# VCA821_AGC.net
KiCad netlist of a schematic drawn in Altium Designer
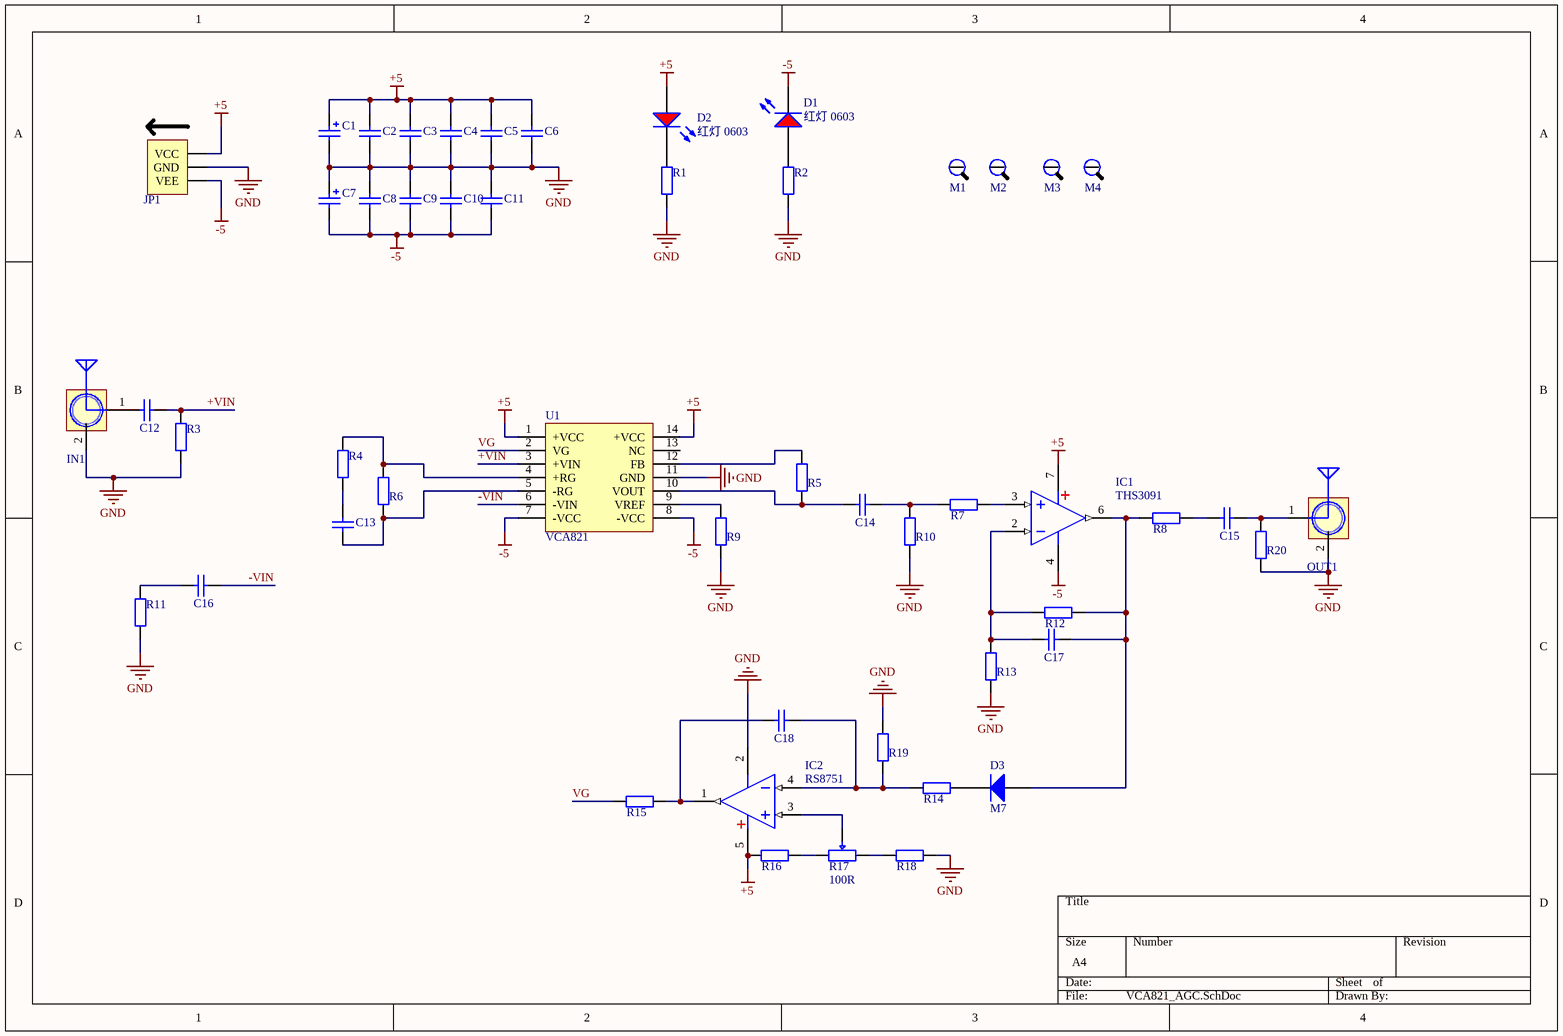
[diagram p0: VCA821_AGC.SchDoc]

(export (version "E")
  (design (tool "Eeschema 10.0.6"))
  (components
    (comp (ref "C1")
      (value "10uF (106) ±10% 16V")
      (footprint "CASE-A_3216")
      (description "钽电容")
      (libsource (lib "JLC") (part "3216 10uF (106) 10% 16V"))
    )
    (comp (ref "C2")
      (value "100nF (104) 10% 50V")
      (footprint "0603_C")
      (description "贴片电容")
      (libsource (lib "JLC") (part "0603 100nF (104) 10% 50V"))
    )
    (comp (ref "C3")
      (value "100nF (104) 10% 50V")
      (footprint "0603_C")
      (description "贴片电容")
      (libsource (lib "JLC") (part "0603 100nF (104) 10% 50V"))
    )
    (comp (ref "C4")
      (value "100nF (104) 10% 50V")
      (footprint "0603_C")
      (description "贴片电容")
      (libsource (lib "JLC") (part "0603 100nF (104) 10% 50V"))
    )
    (comp (ref "C5")
      (value "100nF (104) 10% 50V")
      (footprint "0603_C")
      (description "贴片电容")
      (libsource (lib "JLC") (part "0603 100nF (104) 10% 50V"))
    )
    (comp (ref "C6")
      (value "100nF (104) 10% 50V")
      (footprint "0603_C")
      (description "贴片电容")
      (libsource (lib "JLC") (part "0603 100nF (104) 10% 50V"))
    )
    (comp (ref "C7")
      (value "10uF (106) ±10% 16V")
      (footprint "CASE-A_3216")
      (description "钽电容")
      (libsource (lib "JLC") (part "3216 10uF (106) 10% 16V"))
    )
    (comp (ref "C8")
      (value "100nF (104) 10% 50V")
      (footprint "0603_C")
      (description "贴片电容")
      (libsource (lib "JLC") (part "0603 100nF (104) 10% 50V"))
    )
    (comp (ref "C9")
      (value "100nF (104) 10% 50V")
      (footprint "0603_C")
      (description "贴片电容")
      (libsource (lib "JLC") (part "0603 100nF (104) 10% 50V"))
    )
    (comp (ref "C10")
      (value "100nF (104) 10% 50V")
      (footprint "0603_C")
      (description "贴片电容")
      (libsource (lib "JLC") (part "0603 100nF (104) 10% 50V"))
    )
    (comp (ref "C11")
      (value "100nF (104) 10% 50V")
      (footprint "0603_C")
      (description "贴片电容")
      (libsource (lib "JLC") (part "0603 100nF (104) 10% 50V"))
    )
    (comp (ref "C12")
      (value "100nF (104) 10% 50V")
      (footprint "0603_C")
      (description "贴片电容")
      (libsource (lib "JLC") (part "0603 100nF (104) 10% 50V"))
    )
    (comp (ref "C13")
      (value "100nF (104) 10% 50V")
      (footprint "0603_C")
      (description "贴片电容")
      (libsource (lib "JLC") (part "0603 100nF (104) 10% 50V"))
    )
    (comp (ref "C14")
      (value "100nF (104) 10% 50V")
      (footprint "0603_C")
      (description "贴片电容")
      (libsource (lib "JLC") (part "0603 100nF (104) 10% 50V"))
    )
    (comp (ref "C15")
      (value "100nF (104) 10% 50V")
      (footprint "0603_C")
      (description "贴片电容")
      (libsource (lib "JLC") (part "0603 100nF (104) 10% 50V"))
    )
    (comp (ref "C16")
      (value "100nF (104) 10% 50V")
      (footprint "0603_C")
      (description "贴片电容")
      (libsource (lib "JLC") (part "0603 100nF (104) 10% 50V"))
    )
    (comp (ref "C17")
      (value "100nF (104) 10% 50V")
      (footprint "0603_C")
      (description "贴片电容")
      (libsource (lib "JLC") (part "0603 100nF (104) 10% 50V"))
    )
    (comp (ref "C18")
      (value "100nF (104) 10% 50V")
      (footprint "0603_C")
      (description "贴片电容")
      (libsource (lib "JLC") (part "0603 100nF (104) 10% 50V"))
    )
    (comp (ref "D1")
      (value "红灯 0603")
      (footprint "0603_LED_S1")
      (description "发光二极管")
      (libsource (lib "JLC") (part "0603 红灯"))
    )
    (comp (ref "D2")
      (value "红灯 0603")
      (footprint "0603_LED_S1")
      (description "发光二极管")
      (libsource (lib "JLC") (part "0603 红灯"))
    )
    (comp (ref "D3")
      (value "M7")
      (footprint "SMA(DO-214AC)_S1")
      (description "二极管")
      (libsource (lib "JLC") (part "SMA(DO-214AC) M7"))
    )
    (comp (ref "IC1")
      (value "THS3091")
      (footprint "SOP8_N")
      (description "SOP8_轨至轨运放")
      (fields (field (name "版权归属") "源创客"))
      (libsource (lib "1.5   - 运放-功放") (part "SGM8521-8Pin"))
    )
    (comp (ref "IC2")
      (value "RS8751")
      (footprint "SOT23-5N")
      (description "SOT23-5_轨至轨运放")
      (fields (field (name "版权归属") "源创客"))
      (libsource (lib "1.5   - 运放-功放") (part "SGM8521-5Pin"))
    )
    (comp (ref "IN1")
      (value "SMA WIFI 天线接口")
      (footprint "SMA")
      (description "SMA-2.4G射频天线接口")
      (fields (field (name "版权归属") "源创客"))
      (libsource (lib "") (part "PORT_SMA_1"))
    )
    (comp (ref "JP1")
      (value "HDR-1X3")
      (footprint "Power_IN_3.81-3P")
      (description "3P接插件,模块双电源供电口")
      (fields (field (name "版权归属") "源创客"))
      (libsource (lib "Cooperation") (part "PORT_Power_IN3"))
    )
    (comp (ref "M1")
      (value "M3")
      (footprint "M3x10_L")
      (description "螺丝")
      (libsource (lib "Cooperation") (part "ELSE_M3_screw"))
    )
    (comp (ref "M2")
      (value "M3")
      (footprint "M3x10_L")
      (description "螺丝")
      (libsource (lib "Cooperation") (part "ELSE_M3_screw"))
    )
    (comp (ref "M3")
      (value "M3")
      (footprint "M3x10_L")
      (description "螺丝")
      (libsource (lib "Cooperation") (part "ELSE_M3_screw"))
    )
    (comp (ref "M4")
      (value "M3")
      (footprint "M3x10_L")
      (description "螺丝")
      (libsource (lib "Cooperation") (part "ELSE_M3_screw"))
    )
    (comp (ref "OUT1")
      (value "SMA WIFI 天线接口")
      (footprint "SMA")
      (description "SMA-2.4G射频天线接口")
      (fields (field (name "版权归属") "源创客"))
      (libsource (lib "Cooperation") (part "PORT_SMA"))
    )
    (comp (ref "R1")
      (value "10KΩ (1002) ±1%")
      (footprint "0603_R")
      (description "贴片电阻")
      (libsource (lib "JLC") (part "0603 10KΩ (1002) 1%"))
    )
    (comp (ref "R2")
      (value "10KΩ (1002) ±1%")
      (footprint "0603_R")
      (description "贴片电阻")
      (libsource (lib "JLC") (part "0603 10KΩ (1002) 1%"))
    )
    (comp (ref "R3")
      (value "10KΩ (1002) ±1%")
      (footprint "0603_R")
      (description "贴片电阻")
      (libsource (lib "JLC") (part "0603 10KΩ (1002) 1%"))
    )
    (comp (ref "R4")
      (value "10KΩ (1002) ±1%")
      (footprint "0603_R")
      (description "贴片电阻")
      (libsource (lib "JLC") (part "0603 10KΩ (1002) 1%"))
    )
    (comp (ref "R5")
      (value "10KΩ (1002) ±1%")
      (footprint "0603_R")
      (description "贴片电阻")
      (libsource (lib "") (part "0603 10KΩ (1002) 1%_1"))
    )
    (comp (ref "R6")
      (value "10KΩ (1002) ±1%")
      (footprint "0603_R")
      (description "贴片电阻")
      (libsource (lib "") (part "0603 10KΩ (1002) 1%_1"))
    )
    (comp (ref "R7")
      (value "10KΩ (1002) ±1%")
      (footprint "0603_R")
      (description "贴片电阻")
      (libsource (lib "") (part "0603 10KΩ (1002) 1%_2"))
    )
    (comp (ref "R8")
      (value "10KΩ (1002) ±1%")
      (footprint "0603_R")
      (description "贴片电阻")
      (libsource (lib "") (part "0603 10KΩ (1002) 1%_2"))
    )
    (comp (ref "R9")
      (value "10KΩ (1002) ±1%")
      (footprint "0603_R")
      (description "贴片电阻")
      (libsource (lib "") (part "0603 10KΩ (1002) 1%_1"))
    )
    (comp (ref "R10")
      (value "10KΩ (1002) ±1%")
      (footprint "0603_R")
      (description "贴片电阻")
      (libsource (lib "") (part "0603 10KΩ (1002) 1%_1"))
    )
    (comp (ref "R11")
      (value "10KΩ (1002) ±1%")
      (footprint "0603_R")
      (description "贴片电阻")
      (libsource (lib "JLC") (part "0603 10KΩ (1002) 1%"))
    )
    (comp (ref "R12")
      (value "10KΩ (1002) ±1%")
      (footprint "0603_R")
      (description "贴片电阻")
      (libsource (lib "") (part "0603 10KΩ (1002) 1%_2"))
    )
    (comp (ref "R13")
      (value "10KΩ (1002) ±1%")
      (footprint "0603_R")
      (description "贴片电阻")
      (libsource (lib "") (part "0603 10KΩ (1002) 1%_1"))
    )
    (comp (ref "R14")
      (value "10KΩ (1002) ±1%")
      (footprint "0603_R")
      (description "贴片电阻")
      (libsource (lib "") (part "0603 10KΩ (1002) 1%_2"))
    )
    (comp (ref "R15")
      (value "10KΩ (1002) ±1%")
      (footprint "0603_R")
      (description "贴片电阻")
      (libsource (lib "") (part "0603 10KΩ (1002) 1%_2"))
    )
    (comp (ref "R16")
      (value "10KΩ (1002) ±1%")
      (footprint "0603_R")
      (description "贴片电阻")
      (libsource (lib "") (part "0603 10KΩ (1002) 1%_2"))
    )
    (comp (ref "R17")
      (value "100R")
      (footprint "adjustable resistor")
      (description "adjustable resistor可调电阻")
      (fields (field (name "Comment") "Ω"))
      (libsource (lib "Cooperation") (part "RES_Adjustable_Resistor"))
    )
    (comp (ref "R18")
      (value "10KΩ (1002) ±1%")
      (footprint "0603_R")
      (description "贴片电阻")
      (libsource (lib "") (part "0603 10KΩ (1002) 1%_2"))
    )
    (comp (ref "R19")
      (value "10KΩ (1002) ±1%")
      (footprint "0603_R")
      (description "贴片电阻")
      (libsource (lib "JLC") (part "0603 10KΩ (1002) 1%"))
    )
    (comp (ref "R20")
      (value "10KΩ (1002) ±1%")
      (footprint "0603_R")
      (description "贴片电阻")
      (libsource (lib "JLC") (part "0603 10KΩ (1002) 1%"))
    )
    (comp (ref "U1") (value "VCA821") (footprint "SO-14N") (libsource (lib "Cooperation") (part "VCA821")))
  )
  (nets
    (net (code "1") (name "+5") (class "Default")
      (node (ref "C1") (pin "1") (pinfunction "1_1") (pintype "passive"))
      (node (ref "C2") (pin "2") (pinfunction "2_2") (pintype "passive"))
      (node (ref "C3") (pin "2") (pinfunction "2_2") (pintype "passive"))
      (node (ref "C4") (pin "2") (pinfunction "2_2") (pintype "passive"))
      (node (ref "C5") (pin "2") (pinfunction "2_2") (pintype "passive"))
      (node (ref "C6") (pin "2") (pinfunction "2_2") (pintype "passive"))
      (node (ref "D2") (pin "A") (pinfunction "A_A") (pintype "passive"))
      (node (ref "IC1") (pin "7") (pinfunction "V+_7") (pintype "power_in"))
      (node (ref "IC2") (pin "5") (pinfunction "V+_5") (pintype "power_in"))
      (node (ref "JP1") (pin "1") (pinfunction "VCC_1") (pintype "passive"))
      (node (ref "R16") (pin "1") (pinfunction "1_1") (pintype "passive"))
      (node (ref "U1") (pin "1") (pinfunction "+VCC_1") (pintype "passive"))
      (node (ref "U1") (pin "14") (pinfunction "+VCC_14") (pintype "passive"))
    )
    (net (code "2") (name "-5") (class "Default")
      (node (ref "C10") (pin "1") (pinfunction "1_1") (pintype "passive"))
      (node (ref "C11") (pin "1") (pinfunction "1_1") (pintype "passive"))
      (node (ref "C7") (pin "2") (pinfunction "2_2") (pintype "passive"))
      (node (ref "C8") (pin "1") (pinfunction "1_1") (pintype "passive"))
      (node (ref "C9") (pin "1") (pinfunction "1_1") (pintype "passive"))
      (node (ref "D1") (pin "K") (pinfunction "K_K") (pintype "passive"))
      (node (ref "IC1") (pin "4") (pinfunction "V-_4") (pintype "power_in"))
      (node (ref "JP1") (pin "3") (pinfunction "VEE_3") (pintype "passive"))
      (node (ref "U1") (pin "7") (pinfunction "-VCC_7") (pintype "passive"))
      (node (ref "U1") (pin "8") (pinfunction "-VCC_8") (pintype "passive"))
    )
    (net (code "3") (name "/+VIN") (class "Default")
      (node (ref "C12") (pin "1") (pinfunction "1_1") (pintype "passive"))
      (node (ref "R3") (pin "2") (pinfunction "2_2") (pintype "passive"))
      (node (ref "U1") (pin "3") (pinfunction "+VIN_3") (pintype "passive"))
    )
    (net (code "4") (name "/-VIN") (class "Default")
      (node (ref "C16") (pin "1") (pinfunction "1_1") (pintype "passive"))
      (node (ref "U1") (pin "6") (pinfunction "-VIN_6") (pintype "passive"))
    )
    (net (code "5") (name "/VG") (class "Default")
      (node (ref "R15") (pin "1") (pinfunction "1_1") (pintype "passive"))
      (node (ref "U1") (pin "2") (pinfunction "VG_2") (pintype "passive"))
    )
    (net (code "6") (name "GND") (class "Default")
      (node (ref "C1") (pin "2") (pinfunction "2_2") (pintype "passive"))
      (node (ref "C10") (pin "2") (pinfunction "2_2") (pintype "passive"))
      (node (ref "C11") (pin "2") (pinfunction "2_2") (pintype "passive"))
      (node (ref "C2") (pin "1") (pinfunction "1_1") (pintype "passive"))
      (node (ref "C3") (pin "1") (pinfunction "1_1") (pintype "passive"))
      (node (ref "C4") (pin "1") (pinfunction "1_1") (pintype "passive"))
      (node (ref "C5") (pin "1") (pinfunction "1_1") (pintype "passive"))
      (node (ref "C6") (pin "1") (pinfunction "1_1") (pintype "passive"))
      (node (ref "C7") (pin "1") (pinfunction "1_1") (pintype "passive"))
      (node (ref "C8") (pin "2") (pinfunction "2_2") (pintype "passive"))
      (node (ref "C9") (pin "2") (pinfunction "2_2") (pintype "passive"))
      (node (ref "IC2") (pin "2") (pinfunction "V-_2") (pintype "power_in"))
      (node (ref "IN1") (pin "2") (pinfunction "2_2") (pintype "passive"))
      (node (ref "JP1") (pin "2") (pinfunction "GND_2") (pintype "passive"))
      (node (ref "OUT1") (pin "2") (pinfunction "2_2") (pintype "passive"))
      (node (ref "R1") (pin "1") (pinfunction "1_1") (pintype "passive"))
      (node (ref "R10") (pin "2") (pinfunction "2_2") (pintype "passive"))
      (node (ref "R11") (pin "1") (pinfunction "1_1") (pintype "passive"))
      (node (ref "R13") (pin "2") (pinfunction "2_2") (pintype "passive"))
      (node (ref "R18") (pin "2") (pinfunction "2_2") (pintype "passive"))
      (node (ref "R19") (pin "2") (pinfunction "2_2") (pintype "passive"))
      (node (ref "R2") (pin "1") (pinfunction "1_1") (pintype "passive"))
      (node (ref "R20") (pin "1") (pinfunction "1_1") (pintype "passive"))
      (node (ref "R3") (pin "1") (pinfunction "1_1") (pintype "passive"))
      (node (ref "R9") (pin "2") (pinfunction "2_2") (pintype "passive"))
      (node (ref "U1") (pin "11") (pinfunction "GND_11") (pintype "passive"))
    )
    (net (code "7") (name "Net-(C13-Pad2)") (class "Default")
      (node (ref "C13") (pin "2") (pinfunction "2_2") (pintype "passive"))
      (node (ref "R4") (pin "1") (pinfunction "1_1") (pintype "passive"))
    )
    (net (code "8") (name "Net-(C14-Pad1)") (class "Default")
      (node (ref "C14") (pin "1") (pinfunction "1_1") (pintype "passive"))
      (node (ref "R10") (pin "1") (pinfunction "1_1") (pintype "passive"))
      (node (ref "R7") (pin "1") (pinfunction "1_1") (pintype "passive"))
    )
    (net (code "9") (name "Net-(C15-Pad2)") (class "Default")
      (node (ref "C15") (pin "2") (pinfunction "2_2") (pintype "passive"))
      (node (ref "R8") (pin "2") (pinfunction "2_2") (pintype "passive"))
    )
    (net (code "10") (name "Net-(C16-Pad2)") (class "Default")
      (node (ref "C16") (pin "2") (pinfunction "2_2") (pintype "passive"))
      (node (ref "R11") (pin "2") (pinfunction "2_2") (pintype "passive"))
    )
    (net (code "11") (name "Net-(D1-PadA)") (class "Default")
      (node (ref "D1") (pin "A") (pinfunction "A_A") (pintype "passive"))
      (node (ref "R2") (pin "2") (pinfunction "2_2") (pintype "passive"))
    )
    (net (code "12") (name "Net-(D2-PadK)") (class "Default")
      (node (ref "D2") (pin "K") (pinfunction "K_K") (pintype "passive"))
      (node (ref "R1") (pin "2") (pinfunction "2_2") (pintype "passive"))
    )
    (net (code "13") (name "Net-(D3-A)") (class "Default")
      (node (ref "C17") (pin "1") (pinfunction "1_1") (pintype "passive"))
      (node (ref "D3") (pin "1") (pinfunction "A_1") (pintype "passive"))
      (node (ref "IC1") (pin "6") (pinfunction "OUT_6") (pintype "output"))
      (node (ref "R12") (pin "2") (pinfunction "2_2") (pintype "passive"))
      (node (ref "R8") (pin "1") (pinfunction "1_1") (pintype "passive"))
    )
    (net (code "14") (name "Net-(D3-K)") (class "Default")
      (node (ref "D3") (pin "2") (pinfunction "K_2") (pintype "passive"))
      (node (ref "R14") (pin "2") (pinfunction "2_2") (pintype "passive"))
    )
    (net (code "15") (name "Net-(IC1-IN-)") (class "Default")
      (node (ref "C17") (pin "2") (pinfunction "2_2") (pintype "passive"))
      (node (ref "IC1") (pin "2") (pinfunction "IN-_2") (pintype "input"))
      (node (ref "R12") (pin "1") (pinfunction "1_1") (pintype "passive"))
      (node (ref "R13") (pin "1") (pinfunction "1_1") (pintype "passive"))
    )
    (net (code "16") (name "Net-(IC1-Pad3)") (class "Default")
      (node (ref "IC1") (pin "3") (pinfunction "3_3") (pintype "input"))
      (node (ref "R7") (pin "2") (pinfunction "2_2") (pintype "passive"))
    )
    (net (code "17") (name "Net-(IC2-IN+)") (class "Default")
      (node (ref "IC2") (pin "3") (pinfunction "IN+_3") (pintype "input"))
      (node (ref "R17") (pin "2") (pinfunction "2_2") (pintype "passive"))
    )
    (net (code "18") (name "Net-(IC2-IN-)") (class "Default")
      (node (ref "C18") (pin "1") (pinfunction "1_1") (pintype "passive"))
      (node (ref "IC2") (pin "4") (pinfunction "IN-_4") (pintype "input"))
      (node (ref "R14") (pin "1") (pinfunction "1_1") (pintype "passive"))
      (node (ref "R19") (pin "1") (pinfunction "1_1") (pintype "passive"))
    )
    (net (code "19") (name "Net-(IC2-OUT)") (class "Default")
      (node (ref "C18") (pin "2") (pinfunction "2_2") (pintype "passive"))
      (node (ref "IC2") (pin "1") (pinfunction "OUT_1") (pintype "output"))
      (node (ref "R15") (pin "2") (pinfunction "2_2") (pintype "passive"))
    )
    (net (code "20") (name "Net-(IN1-SINGLE)") (class "Default")
      (node (ref "C12") (pin "2") (pinfunction "2_2") (pintype "passive"))
      (node (ref "IN1") (pin "1") (pinfunction "SINGLE_1") (pintype "passive"))
    )
    (net (code "21") (name "Net-(OUT1-SINGLE)") (class "Default")
      (node (ref "C15") (pin "1") (pinfunction "1_1") (pintype "passive"))
      (node (ref "OUT1") (pin "1") (pinfunction "SINGLE_1") (pintype "passive"))
      (node (ref "R20") (pin "2") (pinfunction "2_2") (pintype "passive"))
    )
    (net (code "22") (name "Net-(R16-Pad2)") (class "Default")
      (node (ref "R16") (pin "2") (pinfunction "2_2") (pintype "passive"))
      (node (ref "R17") (pin "1") (pinfunction "1_1") (pintype "passive"))
    )
    (net (code "23") (name "Net-(R17-Pad3)") (class "Default")
      (node (ref "R17") (pin "3") (pinfunction "3_3") (pintype "passive"))
      (node (ref "R18") (pin "1") (pinfunction "1_1") (pintype "passive"))
    )
    (net (code "24") (name "Net-(U1-+RG)") (class "Default")
      (node (ref "R4") (pin "2") (pinfunction "2_2") (pintype "passive"))
      (node (ref "R6") (pin "1") (pinfunction "1_1") (pintype "passive"))
      (node (ref "U1") (pin "4") (pinfunction "+RG_4") (pintype "passive"))
    )
    (net (code "25") (name "Net-(U1--RG)") (class "Default")
      (node (ref "C13") (pin "1") (pinfunction "1_1") (pintype "passive"))
      (node (ref "R6") (pin "2") (pinfunction "2_2") (pintype "passive"))
      (node (ref "U1") (pin "5") (pinfunction "-RG_5") (pintype "passive"))
    )
    (net (code "26") (name "Net-(U1-FB)") (class "Default")
      (node (ref "R5") (pin "1") (pinfunction "1_1") (pintype "passive"))
      (node (ref "U1") (pin "12") (pinfunction "FB_12") (pintype "passive"))
    )
    (net (code "27") (name "Net-(U1-VOUT)") (class "Default")
      (node (ref "C14") (pin "2") (pinfunction "2_2") (pintype "passive"))
      (node (ref "R5") (pin "2") (pinfunction "2_2") (pintype "passive"))
      (node (ref "U1") (pin "10") (pinfunction "VOUT_10") (pintype "passive"))
    )
    (net (code "28") (name "Net-(U1-VREF)") (class "Default")
      (node (ref "R9") (pin "1") (pinfunction "1_1") (pintype "passive"))
      (node (ref "U1") (pin "9") (pinfunction "VREF_9") (pintype "passive"))
    )
    (net (code "29") (name "unconnected-(M1-Pad1)") (class "Default")
      (node (ref "M1") (pin "1") (pinfunction "1_1") (pintype "passive"))
    )
    (net (code "30") (name "unconnected-(M2-Pad1)") (class "Default")
      (node (ref "M2") (pin "1") (pinfunction "1_1") (pintype "passive"))
    )
    (net (code "31") (name "unconnected-(M3-Pad1)") (class "Default")
      (node (ref "M3") (pin "1") (pinfunction "1_1") (pintype "passive"))
    )
    (net (code "32") (name "unconnected-(M4-Pad1)") (class "Default")
      (node (ref "M4") (pin "1") (pinfunction "1_1") (pintype "passive"))
    )
    (net (code "33") (name "unconnected-(U1-NC-Pad13)") (class "Default")
      (node (ref "U1") (pin "13") (pinfunction "NC_13") (pintype "passive"))
    )
  )
)
